# Sheet1.net
KiCad netlist of a schematic drawn in Altium Designer
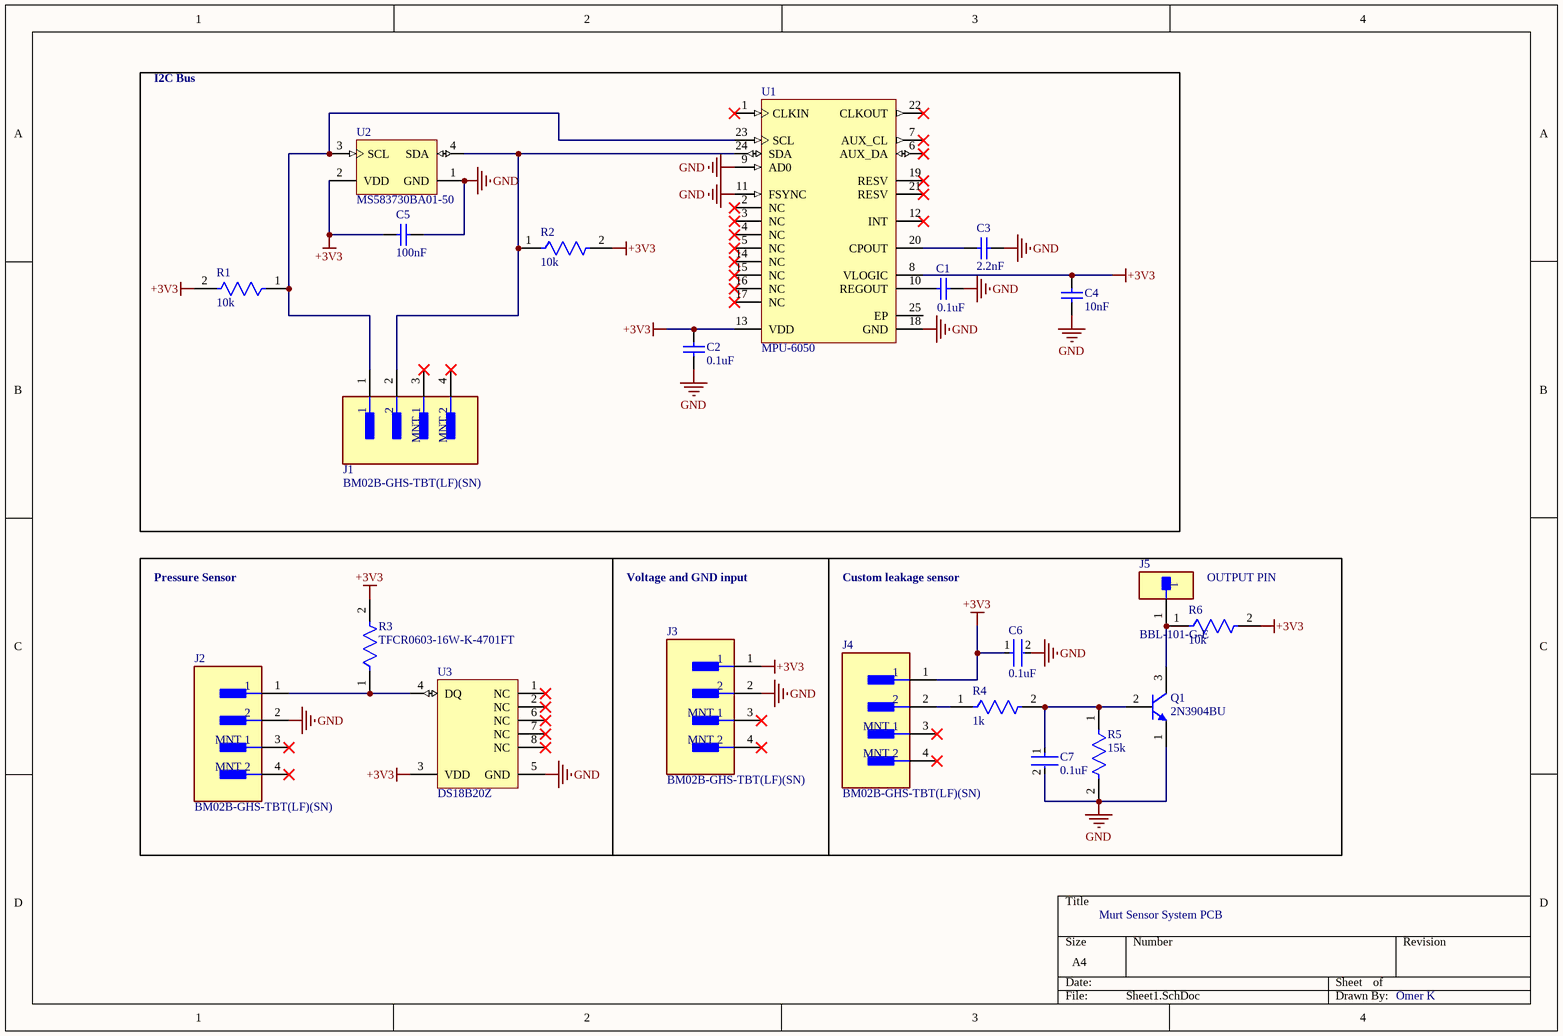
[diagram p0: Sheet1.SchDoc]

(export (version "E")
  (design (tool "Eeschema 10.0.6"))
  (components
    (comp (ref "C1")
      (value "0.1uF")
      (footprint "CAPC2013X145X50ML20T20")
      (fields (field (name "MANUFACTURER") "Vitramon") (field (name "PART NUMBER") "VJ0805Y104KXQCW1BC"))
      (libsource (lib "Altium Content Vault") (part "CAP"))
    )
    (comp (ref "C2")
      (value "0.1uF")
      (footprint "CAPC2013X145X50ML20T20")
      (fields (field (name "MANUFACTURER") "Vitramon") (field (name "PART NUMBER") "VJ0805Y104KXQCW1BC"))
      (libsource (lib "Altium Content Vault") (part "CAP"))
    )
    (comp (ref "C3")
      (value "2.2nF")
      (footprint "CAPC2013X145X50LL20T20")
      (fields (field (name "PART NUMBER") "VJ0805Y222KXQCW1BC") (field (name "MANUFACTURER") "Vitramon"))
      (libsource (lib "Altium Content Vault") (part "CAP"))
    )
    (comp (ref "C4")
      (value "10nF")
      (footprint "CAPC2013X145X50LL20T20")
      (fields (field (name "PART NUMBER") "VJ0805Y103KXQPW1BC") (field (name "MANUFACTURER") "Vitramon"))
      (libsource (lib "Altium Content Vault") (part "CAP"))
    )
    (comp (ref "C5")
      (value "100nF")
      (footprint "CAPC2013X145X50ML20T20")
      (fields (field (name "MANUFACTURER") "Vitramon") (field (name "PART NUMBER") "VJ0805Y104KXQCW1BC"))
      (libsource (lib "Altium Content Vault") (part "CAP"))
    )
    (comp (ref "C6")
      (value "0.1uF")
      (footprint "FP-CC0402-MFG")
      (description "CAP CER 0.1UF 6.3V X7R 0402")
      (fields (field (name "MANUFACTURER") "YAGEO") (field (name "TOLERANCE") "0.1"))
      (libsource (lib "Altium Content Vault") (part "11868f565c42a9108669ba33697ecf6"))
    )
    (comp (ref "C7")
      (value "0.1uF")
      (footprint "FP-CC0402-MFG")
      (description "CAP CER 0.1UF 6.3V X7R 0402")
      (fields (field (name "MANUFACTURER") "YAGEO") (field (name "TOLERANCE") "0.1"))
      (libsource (lib "Altium Content Vault") (part "11868f565c42a9108669ba33697ecf6"))
    )
    (comp (ref "J1")
      (value "BM02B-GHS-TBT(LF)(SN)")
      (footprint "FP-BM02B-GHS-TBT_LF_SN-MFG")
      (description "CONN HEADER SMD 2POS 1.25MM")
      (libsource (lib "") (part "6ebc6fc72a9fd5a6899c7600f385cff_1"))
    )
    (comp (ref "J2")
      (value "BM02B-GHS-TBT(LF)(SN)")
      (footprint "FP-BM02B-GHS-TBT_LF_SN-MFG")
      (description "CONN HEADER SMD 2POS 1.25MM")
      (libsource (lib "Altium Content Vault") (part "6ebc6fc72a9fd5a6899c7600f385cff"))
    )
    (comp (ref "J3")
      (value "BM02B-GHS-TBT(LF)(SN)")
      (footprint "FP-BM02B-GHS-TBT_LF_SN-MFG")
      (description "CONN HEADER SMD 2POS 1.25MM")
      (libsource (lib "Altium Content Vault") (part "6ebc6fc72a9fd5a6899c7600f385cff"))
    )
    (comp (ref "J4")
      (value "BM02B-GHS-TBT(LF)(SN)")
      (footprint "FP-BM02B-GHS-TBT_LF_SN-MFG")
      (description "CONN HEADER SMD 2POS 1.25MM")
      (libsource (lib "Altium Content Vault") (part "6ebc6fc72a9fd5a6899c7600f385cff"))
    )
    (comp (ref "J5")
      (value "BBL-101-G-E")
      (footprint "FP-BBL-101-G-E-MFG")
      (description "BBL-101-G-E Conn Unshrouded Header HDR 1 POS Solder ST Top Entry Thru-Hole Bulk")
      (libsource (lib "Altium Content Vault") (part "dd45045ce8184df9e99e12baf3f412c"))
    )
    (comp (ref "Q1")
      (value "2N3904BU")
      (footprint "FAIR-TO-92")
      (description "NPN General-Purpose Amplifier, 40 V VCEO, 0.2 A, -55 to 150 degC, 2-Pin TO-92, RoHS, Bulk")
      (fields (field (name "MANUFACTURER") "FairchildSemiconductor"))
      (libsource (lib "Altium Content Vault") (part "NPN-E1B2C3-3"))
    )
    (comp (ref "R1")
      (value "10k")
      (footprint "FP-AC0603-MFG")
      (description "RES 10kΩ 1.00% 0.2W 0603")
      (libsource (lib "Altium Content Vault") (part "1029c3af85768c4190bb7ad29bc67b5"))
    )
    (comp (ref "R2")
      (value "10k")
      (footprint "FP-AC0603-MFG")
      (description "RES 10kΩ 1.00% 0.2W 0603")
      (libsource (lib "Altium Content Vault") (part "1029c3af85768c4190bb7ad29bc67b5"))
    )
    (comp (ref "R3")
      (value "TFCR0603-16W-K-4701FT")
      (footprint "FP-TFCR0603-IPC_C")
      (description "RES Thin Film,  4.7kΩ, 1%, 0.1W, 100ppm/°C, 0603")
      (libsource (lib "Altium Content Vault") (part "1029c3af85768c4190bb7ad29bc67b5"))
    )
    (comp (ref "R4")
      (value "1k")
      (footprint "FP-TFCR0805-IPC_A")
      (description "RES Thin Film,  1kΩ, 0.1%, 0.1W, 25ppm/°C, 0805")
      (libsource (lib "Altium Content Vault") (part "1029c3af85768c4190bb7ad29bc67b5"))
    )
    (comp (ref "R5")
      (value "15k")
      (footprint "FP-CRGCQ0805-IPC_C")
      (description "CRGCQ 0805 15K 1%")
      (fields (field (name "TOLERANCE") "0.01") (field (name "MANUFACTURER PART NUMBER") "CRGCQ0805F15K"))
      (libsource (lib "Altium Content Vault") (part "1029c3af85768c4190bb7ad29bc67b5"))
    )
    (comp (ref "R6")
      (value "10k")
      (footprint "FP-CRGCQ0805-IPC_C")
      (description "CRGCQ 0805 10K 5%")
      (fields
        (field (name "MANUFACTURER PART NUMBER") "CRGCQ0805J10K")
        (field (name "MANUFACTURER") "TE Connectivity")
      )
      (libsource (lib "Altium Content Vault") (part "1029c3af85768c4190bb7ad29bc67b5"))
    )
    (comp (ref "U1")
      (value "MPU-6050")
      (footprint "IS-QFN-24_V")
      (fields (field (name "MANUFACTURER") "InvenSense"))
      (libsource (lib "Altium Content Vault") (part "IS-MPU-6050-QFN-24"))
    )
    (comp (ref "U2")
      (value "MS583730BA01-50")
      (footprint "TECO-MS583730BA01-50_V")
      (fields (field (name "MANUFACTURER") "TE Connectivity"))
      (libsource (lib "Altium Content Vault") (part "TECO-MS583730BA01-50-4"))
    )
    (comp (ref "U3")
      (value "DS18B20Z")
      (footprint "MAXM-S8-2_N")
      (description "High-Precision 1-Wire Digital Thermometer, -55 to 125 degC, 8-Pin SOIC (S8-2)")
      (fields (field (name "GENERIC PART NUMBER") "DS18B20"))
      (libsource (lib "Altium Content Vault") (part "DS18B20-S8-2"))
    )
  )
  (nets
    (net (code "1") (name "+3V3") (class "Default")
      (node (ref "C2") (pin "1") (pinfunction "1_1") (pintype "passive"))
      (node (ref "C4") (pin "1") (pinfunction "1_1") (pintype "passive"))
      (node (ref "C5") (pin "1") (pinfunction "1_1") (pintype "passive"))
      (node (ref "C6") (pin "1") (pinfunction "1_1") (pintype "passive"))
      (node (ref "J3") (pin "1") (pinfunction "1_1") (pintype "passive"))
      (node (ref "J4") (pin "1") (pinfunction "1_1") (pintype "passive"))
      (node (ref "R1") (pin "2") (pinfunction "2_2") (pintype "passive"))
      (node (ref "R2") (pin "2") (pinfunction "2_2") (pintype "passive"))
      (node (ref "R3") (pin "2") (pinfunction "2_2") (pintype "passive"))
      (node (ref "R6") (pin "2") (pinfunction "2_2") (pintype "passive"))
      (node (ref "U1") (pin "13") (pinfunction "VDD_13") (pintype "power_in"))
      (node (ref "U1") (pin "8") (pinfunction "VLOGIC_8") (pintype "power_in"))
      (node (ref "U2") (pin "2") (pinfunction "VDD_2") (pintype "power_in"))
      (node (ref "U3") (pin "3") (pinfunction "VDD_3") (pintype "power_in"))
    )
    (net (code "2") (name "GND") (class "Default")
      (node (ref "C1") (pin "2") (pinfunction "2_2") (pintype "passive"))
      (node (ref "C2") (pin "2") (pinfunction "2_2") (pintype "passive"))
      (node (ref "C3") (pin "2") (pinfunction "2_2") (pintype "passive"))
      (node (ref "C4") (pin "2") (pinfunction "2_2") (pintype "passive"))
      (node (ref "C5") (pin "2") (pinfunction "2_2") (pintype "passive"))
      (node (ref "C6") (pin "2") (pinfunction "2_2") (pintype "passive"))
      (node (ref "C7") (pin "2") (pinfunction "2_2") (pintype "passive"))
      (node (ref "J2") (pin "2") (pinfunction "2_2") (pintype "passive"))
      (node (ref "J3") (pin "2") (pinfunction "2_2") (pintype "passive"))
      (node (ref "Q1") (pin "1") (pinfunction "E_1") (pintype "passive"))
      (node (ref "R5") (pin "2") (pinfunction "2_2") (pintype "passive"))
      (node (ref "U1") (pin "11") (pinfunction "FSYNC_11") (pintype "input"))
      (node (ref "U1") (pin "18") (pinfunction "GND_18") (pintype "power_in"))
      (node (ref "U1") (pin "9") (pinfunction "AD0_9") (pintype "input"))
      (node (ref "U2") (pin "1") (pinfunction "GND_1") (pintype "power_in"))
      (node (ref "U3") (pin "5") (pinfunction "GND_5") (pintype "power_in"))
    )
    (net (code "3") (name "Net-(J4-Pad2)") (class "Default")
      (node (ref "J4") (pin "2") (pinfunction "2_2") (pintype "passive"))
      (node (ref "R4") (pin "1") (pinfunction "1_1") (pintype "passive"))
    )
    (net (code "4") (name "Net-(Q1-B)") (class "Default")
      (node (ref "C7") (pin "1") (pinfunction "1_1") (pintype "passive"))
      (node (ref "Q1") (pin "2") (pinfunction "B_2") (pintype "passive"))
      (node (ref "R4") (pin "2") (pinfunction "2_2") (pintype "passive"))
      (node (ref "R5") (pin "1") (pinfunction "1_1") (pintype "passive"))
    )
    (net (code "5") (name "Net-(Q1-C)") (class "Default")
      (node (ref "J5") (pin "1") (pinfunction "1_1") (pintype "passive"))
      (node (ref "Q1") (pin "3") (pinfunction "C_3") (pintype "passive"))
      (node (ref "R6") (pin "1") (pinfunction "1_1") (pintype "passive"))
    )
    (net (code "6") (name "Net-(U1-CPOUT)") (class "Default")
      (node (ref "C3") (pin "1") (pinfunction "1_1") (pintype "passive"))
      (node (ref "U1") (pin "20") (pinfunction "CPOUT_20") (pintype "passive"))
    )
    (net (code "7") (name "Net-(U1-REGOUT)") (class "Default")
      (node (ref "C1") (pin "1") (pinfunction "1_1") (pintype "passive"))
      (node (ref "U1") (pin "10") (pinfunction "REGOUT_10") (pintype "passive"))
    )
    (net (code "8") (name "Net-(U1-SCL)") (class "Default")
      (node (ref "J1") (pin "1") (pinfunction "1_1") (pintype "passive"))
      (node (ref "R1") (pin "1") (pinfunction "1_1") (pintype "passive"))
      (node (ref "U1") (pin "23") (pinfunction "SCL_23") (pintype "input"))
      (node (ref "U2") (pin "3") (pinfunction "SCL_3") (pintype "input"))
    )
    (net (code "9") (name "Net-(U1-SDA)") (class "Default")
      (node (ref "J1") (pin "2") (pinfunction "2_2") (pintype "passive"))
      (node (ref "R2") (pin "1") (pinfunction "1_1") (pintype "passive"))
      (node (ref "U1") (pin "24") (pinfunction "SDA_24") (pintype "bidirectional"))
      (node (ref "U2") (pin "4") (pinfunction "SDA_4") (pintype "bidirectional"))
    )
    (net (code "10") (name "Net-(U3-DQ)") (class "Default")
      (node (ref "J2") (pin "1") (pinfunction "1_1") (pintype "passive"))
      (node (ref "R3") (pin "1") (pinfunction "1_1") (pintype "passive"))
      (node (ref "U3") (pin "4") (pinfunction "DQ_4") (pintype "bidirectional"))
    )
    (net (code "11") (name "unconnected-(J1-MNT_1-Pad3)") (class "Default")
      (node (ref "J1") (pin "3") (pinfunction "MNT_1_3") (pintype "passive+no_connect"))
    )
    (net (code "12") (name "unconnected-(J1-MNT_2-Pad4)") (class "Default")
      (node (ref "J1") (pin "4") (pinfunction "MNT_2_4") (pintype "passive+no_connect"))
    )
    (net (code "13") (name "unconnected-(J2-MNT_1-Pad3)") (class "Default")
      (node (ref "J2") (pin "3") (pinfunction "MNT_1_3") (pintype "passive+no_connect"))
    )
    (net (code "14") (name "unconnected-(J2-MNT_2-Pad4)") (class "Default")
      (node (ref "J2") (pin "4") (pinfunction "MNT_2_4") (pintype "passive+no_connect"))
    )
    (net (code "15") (name "unconnected-(J3-MNT_1-Pad3)") (class "Default")
      (node (ref "J3") (pin "3") (pinfunction "MNT_1_3") (pintype "passive+no_connect"))
    )
    (net (code "16") (name "unconnected-(J3-MNT_2-Pad4)") (class "Default")
      (node (ref "J3") (pin "4") (pinfunction "MNT_2_4") (pintype "passive+no_connect"))
    )
    (net (code "17") (name "unconnected-(J4-MNT_1-Pad3)") (class "Default")
      (node (ref "J4") (pin "3") (pinfunction "MNT_1_3") (pintype "passive+no_connect"))
    )
    (net (code "18") (name "unconnected-(J4-MNT_2-Pad4)") (class "Default")
      (node (ref "J4") (pin "4") (pinfunction "MNT_2_4") (pintype "passive+no_connect"))
    )
    (net (code "19") (name "unconnected-(U1-AUX_CL-Pad7)") (class "Default")
      (node (ref "U1") (pin "7") (pinfunction "AUX_CL_7") (pintype "output+no_connect"))
    )
    (net (code "20") (name "unconnected-(U1-AUX_DA-Pad6)") (class "Default")
      (node (ref "U1") (pin "6") (pinfunction "AUX_DA_6") (pintype "bidirectional+no_connect"))
    )
    (net (code "21") (name "unconnected-(U1-CLKIN-Pad1)") (class "Default")
      (node (ref "U1") (pin "1") (pinfunction "CLKIN_1") (pintype "input+no_connect"))
    )
    (net (code "22") (name "unconnected-(U1-CLKOUT-Pad22)") (class "Default")
      (node (ref "U1") (pin "22") (pinfunction "CLKOUT_22") (pintype "output+no_connect"))
    )
    (net (code "23") (name "unconnected-(U1-EP-Pad25)") (class "Default")
      (node (ref "U1") (pin "25") (pinfunction "EP_25") (pintype "power_in"))
    )
    (net (code "24") (name "unconnected-(U1-INT-Pad12)") (class "Default")
      (node (ref "U1") (pin "12") (pinfunction "INT_12") (pintype "open_collector+no_connect"))
    )
    (net (code "25") (name "unconnected-(U1-NC-Pad2)") (class "Default")
      (node (ref "U1") (pin "2") (pinfunction "NC_2") (pintype "passive+no_connect"))
    )
    (net (code "26") (name "unconnected-(U1-NC-Pad3)") (class "Default")
      (node (ref "U1") (pin "3") (pinfunction "NC_3") (pintype "passive+no_connect"))
    )
    (net (code "27") (name "unconnected-(U1-NC-Pad4)") (class "Default")
      (node (ref "U1") (pin "4") (pinfunction "NC_4") (pintype "passive+no_connect"))
    )
    (net (code "28") (name "unconnected-(U1-NC-Pad5)") (class "Default")
      (node (ref "U1") (pin "5") (pinfunction "NC_5") (pintype "passive+no_connect"))
    )
    (net (code "29") (name "unconnected-(U1-NC-Pad14)") (class "Default")
      (node (ref "U1") (pin "14") (pinfunction "NC_14") (pintype "passive+no_connect"))
    )
    (net (code "30") (name "unconnected-(U1-NC-Pad15)") (class "Default")
      (node (ref "U1") (pin "15") (pinfunction "NC_15") (pintype "passive+no_connect"))
    )
    (net (code "31") (name "unconnected-(U1-NC-Pad16)") (class "Default")
      (node (ref "U1") (pin "16") (pinfunction "NC_16") (pintype "passive+no_connect"))
    )
    (net (code "32") (name "unconnected-(U1-NC-Pad17)") (class "Default")
      (node (ref "U1") (pin "17") (pinfunction "NC_17") (pintype "passive+no_connect"))
    )
    (net (code "33") (name "unconnected-(U1-RESV-Pad19)") (class "Default")
      (node (ref "U1") (pin "19") (pinfunction "RESV_19") (pintype "passive+no_connect"))
    )
    (net (code "34") (name "unconnected-(U1-RESV-Pad21)") (class "Default")
      (node (ref "U1") (pin "21") (pinfunction "RESV_21") (pintype "passive+no_connect"))
    )
    (net (code "35") (name "unconnected-(U3-NC-Pad1)") (class "Default")
      (node (ref "U3") (pin "1") (pinfunction "NC_1") (pintype "passive+no_connect"))
    )
    (net (code "36") (name "unconnected-(U3-NC-Pad2)") (class "Default")
      (node (ref "U3") (pin "2") (pinfunction "NC_2") (pintype "passive+no_connect"))
    )
    (net (code "37") (name "unconnected-(U3-NC-Pad6)") (class "Default")
      (node (ref "U3") (pin "6") (pinfunction "NC_6") (pintype "passive+no_connect"))
    )
    (net (code "38") (name "unconnected-(U3-NC-Pad7)") (class "Default")
      (node (ref "U3") (pin "7") (pinfunction "NC_7") (pintype "passive+no_connect"))
    )
    (net (code "39") (name "unconnected-(U3-NC-Pad8)") (class "Default")
      (node (ref "U3") (pin "8") (pinfunction "NC_8") (pintype "passive+no_connect"))
    )
  )
)
